# Onju-Home.net
KiCad netlist of a schematic drawn in Altium Designer
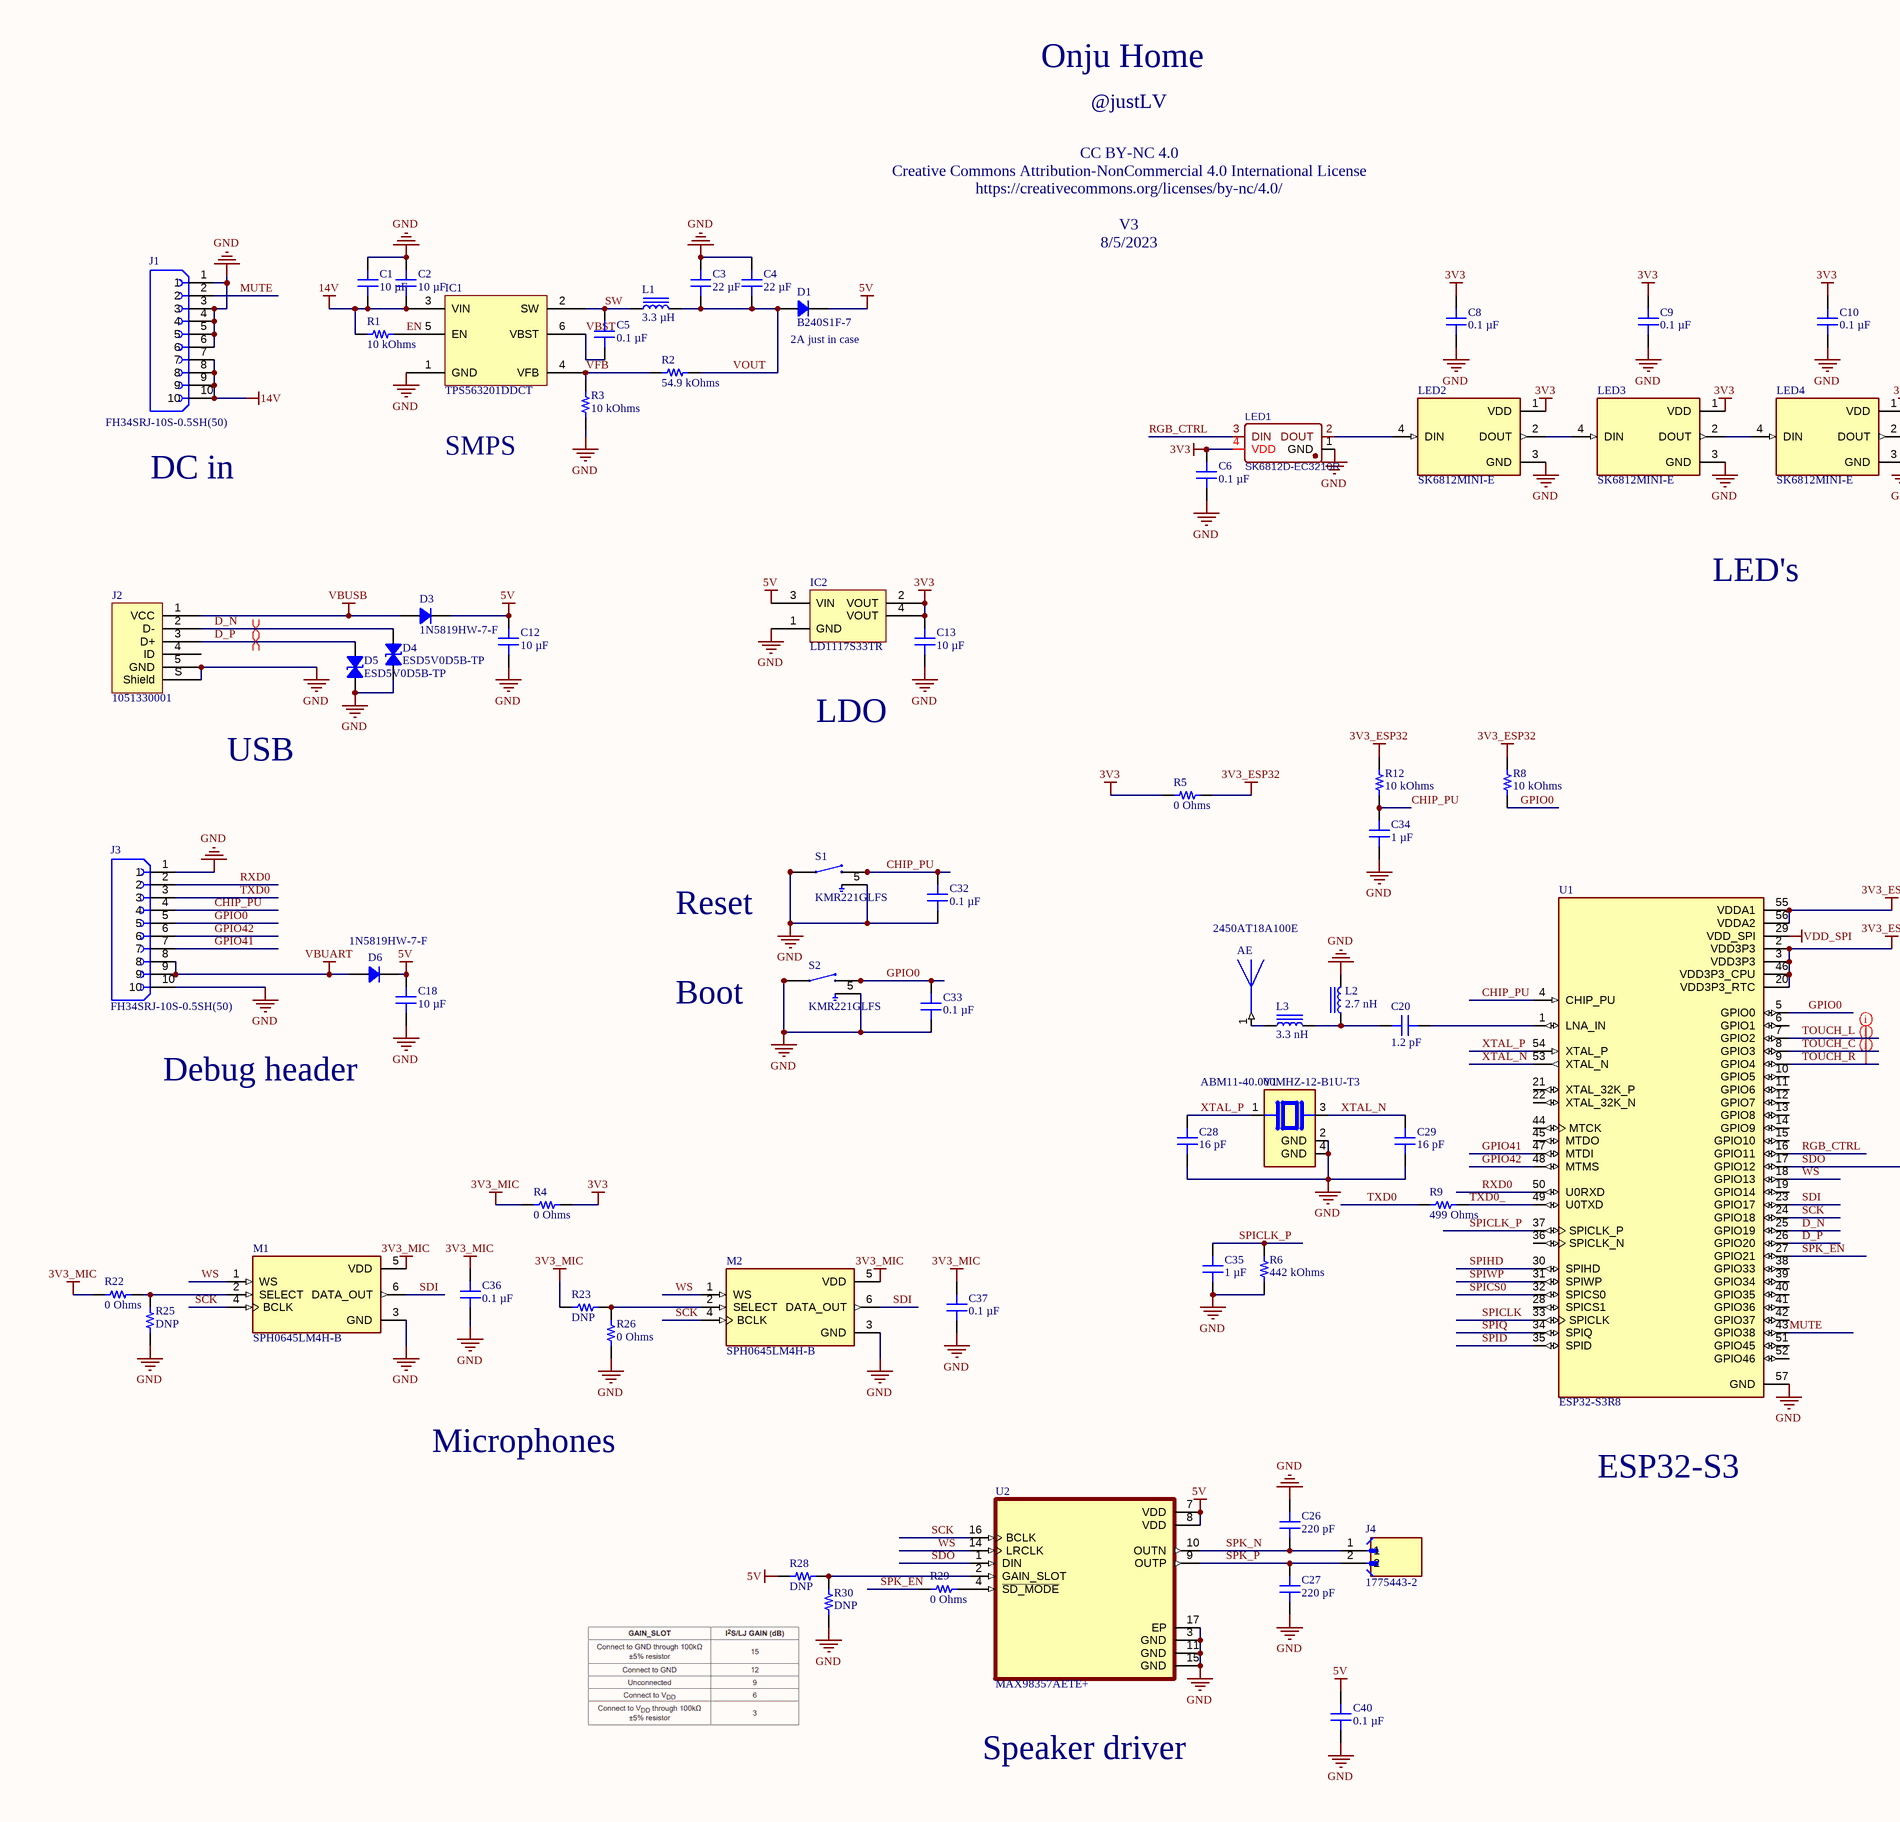
[diagram p0: Onju-Home.SchDoc, left]
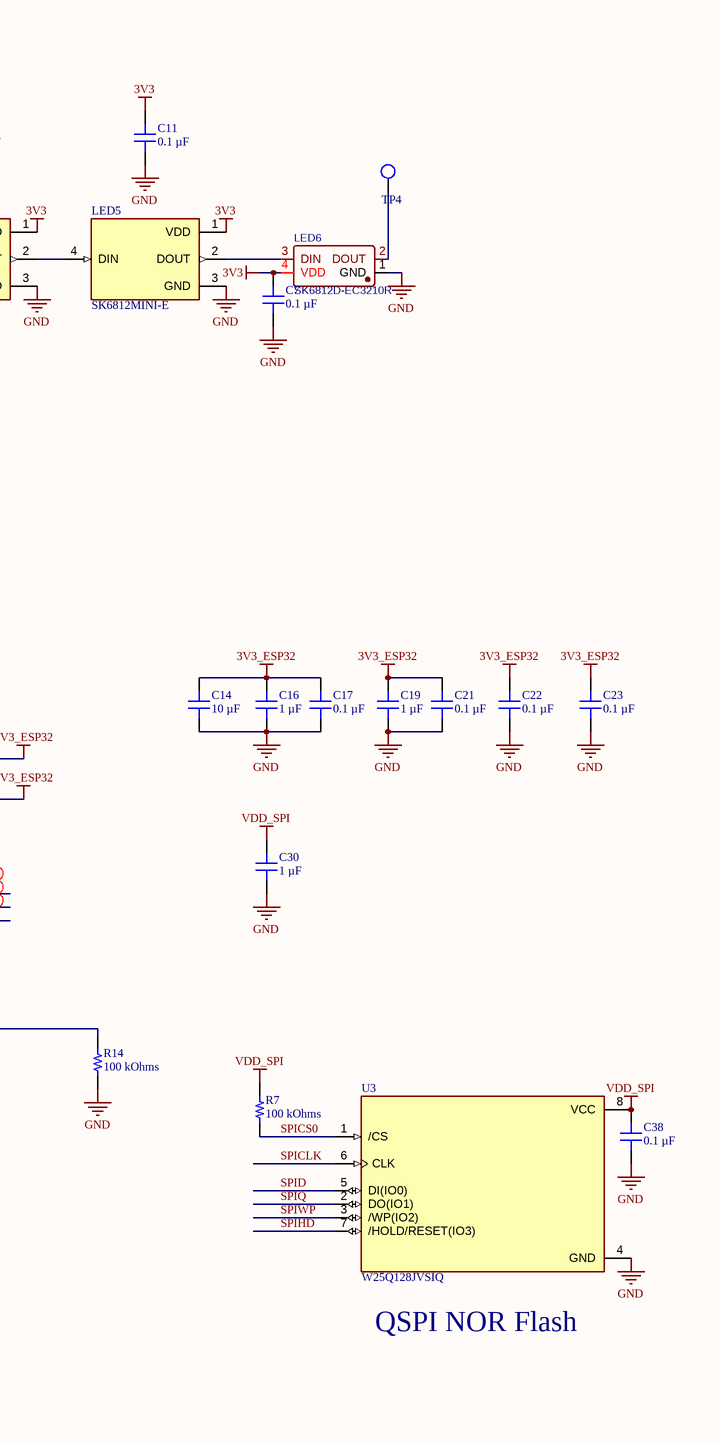
[diagram p1: Onju-Home.SchDoc, right]

(export (version "E")
  (design (tool "Eeschema 10.0.6"))
  (components
    (comp (ref "AE")
      (value "2450AT18A100E")
      (footprint "ANTC3216X140N")
      (description "2.4GHz Chip RF Antenna 2.4GHz ~ 2.5GHz 0.5dBi Solder Surface Mount")
      (fields (field (name "MF") "Johanson Technology") (field (name "JLC PART NUMBER") "C89334"))
      (libsource (lib "Schlib1") (part "2450AT18A100E"))
    )
    (comp (ref "C1")
      (value "10 µF")
      (footprint "CAP 0805_2012")
      (description "CAP CER 10UF 16V X5R 0805")
      (fields
        (field (name "PART NUMBER") "CL21A106KOQNNNE")
        (field (name "MANUFACTURER") "Samsung Electro-Mechanics")
      )
      (libsource (lib "Celestial Altium Library - altium_library") (part "Capacitor"))
    )
    (comp (ref "C2")
      (value "10 µF")
      (footprint "CAP 0805_2012")
      (description "CAP CER 10UF 16V X5R 0805")
      (fields
        (field (name "PART NUMBER") "CL21A106KOQNNNE")
        (field (name "MANUFACTURER") "Samsung Electro-Mechanics")
      )
      (libsource (lib "Celestial Altium Library - altium_library") (part "Capacitor"))
    )
    (comp (ref "C3")
      (value "22 µF")
      (footprint "CAP 0805_2012")
      (description "CAP CER 22UF 25V X5R 0805")
      (fields
        (field (name "PART NUMBER") "CL21A226MAYNNNE")
        (field (name "MANUFACTURER") "Samsung Electro-Mechanics")
      )
      (libsource (lib "Celestial Altium Library - altium_library") (part "Capacitor"))
    )
    (comp (ref "C4")
      (value "22 µF")
      (footprint "CAP 0805_2012")
      (description "CAP CER 22UF 25V X5R 0805")
      (fields
        (field (name "PART NUMBER") "CL21A226MAYNNNE")
        (field (name "MANUFACTURER") "Samsung Electro-Mechanics")
      )
      (libsource (lib "Celestial Altium Library - altium_library") (part "Capacitor"))
    )
    (comp (ref "C5")
      (value "0.1 µF")
      (footprint "CAP 0402_1005")
      (description "CAP CER 0.1UF 25V X5R 0402")
      (fields
        (field (name "PART NUMBER") "CL05A104KA5NNNC")
        (field (name "MANUFACTURER") "Samsung Electro-Mechanics")
      )
      (libsource (lib "Celestial Altium Library - altium_library") (part "Capacitor"))
    )
    (comp (ref "C6")
      (value "0.1 µF")
      (footprint "CAP 0402_1005")
      (description "CAP CER 0.1UF 25V X5R 0402")
      (fields
        (field (name "PART NUMBER") "CL05A104KA5NNNC")
        (field (name "MANUFACTURER") "Samsung Electro-Mechanics")
      )
      (libsource (lib "Celestial Altium Library - altium_library") (part "Capacitor"))
    )
    (comp (ref "C7")
      (value "0.1 µF")
      (footprint "CAP 0402_1005")
      (description "CAP CER 0.1UF 25V X5R 0402")
      (fields
        (field (name "PART NUMBER") "CL05A104KA5NNNC")
        (field (name "MANUFACTURER") "Samsung Electro-Mechanics")
      )
      (libsource (lib "Celestial Altium Library - altium_library") (part "Capacitor"))
    )
    (comp (ref "C8")
      (value "0.1 µF")
      (footprint "CAP 0402_1005")
      (description "CAP CER 0.1UF 25V X5R 0402")
      (fields
        (field (name "PART NUMBER") "CL05A104KA5NNNC")
        (field (name "MANUFACTURER") "Samsung Electro-Mechanics")
      )
      (libsource (lib "Celestial Altium Library - altium_library") (part "Capacitor"))
    )
    (comp (ref "C9")
      (value "0.1 µF")
      (footprint "CAP 0402_1005")
      (description "CAP CER 0.1UF 25V X5R 0402")
      (fields
        (field (name "PART NUMBER") "CL05A104KA5NNNC")
        (field (name "MANUFACTURER") "Samsung Electro-Mechanics")
      )
      (libsource (lib "Celestial Altium Library - altium_library") (part "Capacitor"))
    )
    (comp (ref "C10")
      (value "0.1 µF")
      (footprint "CAP 0402_1005")
      (description "CAP CER 0.1UF 25V X5R 0402")
      (fields
        (field (name "PART NUMBER") "CL05A104KA5NNNC")
        (field (name "MANUFACTURER") "Samsung Electro-Mechanics")
      )
      (libsource (lib "Celestial Altium Library - altium_library") (part "Capacitor"))
    )
    (comp (ref "C11")
      (value "0.1 µF")
      (footprint "CAP 0402_1005")
      (description "CAP CER 0.1UF 25V X5R 0402")
      (fields
        (field (name "PART NUMBER") "CL05A104KA5NNNC")
        (field (name "MANUFACTURER") "Samsung Electro-Mechanics")
      )
      (libsource (lib "Celestial Altium Library - altium_library") (part "Capacitor"))
    )
    (comp (ref "C12")
      (value "10 µF")
      (footprint "CAP 0805_2012")
      (description "CAP CER 10UF 16V X5R 0805")
      (fields
        (field (name "PART NUMBER") "CL21A106KOQNNNE")
        (field (name "MANUFACTURER") "Samsung Electro-Mechanics")
      )
      (libsource (lib "Celestial Altium Library - altium_library") (part "Capacitor"))
    )
    (comp (ref "C13")
      (value "10 µF")
      (footprint "CAP 0805_2012")
      (description "CAP CER 10UF 16V X5R 0805")
      (fields
        (field (name "PART NUMBER") "CL21A106KOQNNNE")
        (field (name "MANUFACTURER") "Samsung Electro-Mechanics")
      )
      (libsource (lib "Celestial Altium Library - altium_library") (part "Capacitor"))
    )
    (comp (ref "C14")
      (value "10 µF")
      (footprint "CAP 0805_2012")
      (description "CAP CER 10UF 16V X5R 0805")
      (fields
        (field (name "PART NUMBER") "CL21A106KOQNNNE")
        (field (name "MANUFACTURER") "Samsung Electro-Mechanics")
      )
      (libsource (lib "Celestial Altium Library - altium_library") (part "Capacitor"))
    )
    (comp (ref "C16")
      (value "1 µF")
      (footprint "CAP 0402_1005")
      (description "CAP CER 1UF 25V X5R 0402")
      (fields
        (field (name "PART NUMBER") "GRM155R61E105MA12J")
        (field (name "MANUFACTURER") "Murata Electronics")
      )
      (libsource (lib "Celestial Altium Library - altium_library") (part "Capacitor"))
    )
    (comp (ref "C17")
      (value "0.1 µF")
      (footprint "CAP 0402_1005")
      (description "CAP CER 0.1UF 25V X5R 0402")
      (fields
        (field (name "PART NUMBER") "CL05A104KA5NNNC")
        (field (name "MANUFACTURER") "Samsung Electro-Mechanics")
      )
      (libsource (lib "Celestial Altium Library - altium_library") (part "Capacitor"))
    )
    (comp (ref "C18")
      (value "10 µF")
      (footprint "CAP 0805_2012")
      (description "CAP CER 10UF 16V X5R 0805")
      (fields
        (field (name "PART NUMBER") "CL21A106KOQNNNE")
        (field (name "MANUFACTURER") "Samsung Electro-Mechanics")
      )
      (libsource (lib "Celestial Altium Library - altium_library") (part "Capacitor"))
    )
    (comp (ref "C19")
      (value "1 µF")
      (footprint "CAP 0402_1005")
      (description "CAP CER 1UF 25V X5R 0402")
      (fields
        (field (name "PART NUMBER") "GRM155R61E105MA12J")
        (field (name "MANUFACTURER") "Murata Electronics")
      )
      (libsource (lib "Celestial Altium Library - altium_library") (part "Capacitor"))
    )
    (comp (ref "C20")
      (value "1.2 pF")
      (footprint "CAP 0402_1005")
      (description "CAP CER 1.2PF 50V C0G/NP0 0402")
      (fields
        (field (name "PART NUMBER") "500R07S1R2BV4T")
        (field (name "MANUFACTURER") "Johanson Technology Inc.")
      )
      (libsource (lib "Celestial Altium Library - altium_library") (part "Capacitor"))
    )
    (comp (ref "C21")
      (value "0.1 µF")
      (footprint "CAP 0402_1005")
      (description "CAP CER 0.1UF 25V X5R 0402")
      (fields
        (field (name "PART NUMBER") "CL05A104KA5NNNC")
        (field (name "MANUFACTURER") "Samsung Electro-Mechanics")
      )
      (libsource (lib "Celestial Altium Library - altium_library") (part "Capacitor"))
    )
    (comp (ref "C22")
      (value "0.1 µF")
      (footprint "CAP 0402_1005")
      (description "CAP CER 0.1UF 25V X5R 0402")
      (fields
        (field (name "PART NUMBER") "CL05A104KA5NNNC")
        (field (name "MANUFACTURER") "Samsung Electro-Mechanics")
      )
      (libsource (lib "Celestial Altium Library - altium_library") (part "Capacitor"))
    )
    (comp (ref "C23")
      (value "0.1 µF")
      (footprint "CAP 0402_1005")
      (description "CAP CER 0.1UF 25V X5R 0402")
      (fields
        (field (name "PART NUMBER") "CL05A104KA5NNNC")
        (field (name "MANUFACTURER") "Samsung Electro-Mechanics")
      )
      (libsource (lib "Celestial Altium Library - altium_library") (part "Capacitor"))
    )
    (comp (ref "C26")
      (value "220 pF")
      (footprint "CAP 0603_1608")
      (description "CAP CER 220PF 50V X7R 0603")
      (fields
        (field (name "PART NUMBER") "CL10B221KB8NFNC")
        (field (name "MANUFACTURER") "Samsung Electro-Mechanics")
      )
      (libsource (lib "Celestial Altium Library - altium_library") (part "Capacitor"))
    )
    (comp (ref "C27")
      (value "220 pF")
      (footprint "CAP 0603_1608")
      (description "CAP CER 220PF 50V X7R 0603")
      (fields
        (field (name "PART NUMBER") "CL10B221KB8NFNC")
        (field (name "MANUFACTURER") "Samsung Electro-Mechanics")
      )
      (libsource (lib "Celestial Altium Library - altium_library") (part "Capacitor"))
    )
    (comp (ref "C28")
      (value "16 pF")
      (footprint "CAP 0402_1005")
      (description "CAP CER 16PF 50V C0G/NP0 0402")
      (fields
        (field (name "PART NUMBER") "GCM1555C1H160FA16D")
        (field (name "MANUFACTURER") "Murata Electronics")
      )
      (libsource (lib "Celestial Altium Library - altium_library") (part "Capacitor"))
    )
    (comp (ref "C29")
      (value "16 pF")
      (footprint "CAP 0402_1005")
      (description "CAP CER 16PF 50V C0G/NP0 0402")
      (fields
        (field (name "PART NUMBER") "GCM1555C1H160FA16D")
        (field (name "MANUFACTURER") "Murata Electronics")
      )
      (libsource (lib "Celestial Altium Library - altium_library") (part "Capacitor"))
    )
    (comp (ref "C30")
      (value "1 µF")
      (footprint "CAP 0402_1005")
      (description "CAP CER 1UF 25V X5R 0402")
      (fields
        (field (name "PART NUMBER") "GRM155R61E105MA12J")
        (field (name "MANUFACTURER") "Murata Electronics")
      )
      (libsource (lib "Celestial Altium Library - altium_library") (part "Capacitor"))
    )
    (comp (ref "C32")
      (value "0.1 µF")
      (footprint "CAP 0402_1005")
      (description "CAP CER 0.1UF 25V X5R 0402")
      (fields
        (field (name "PART NUMBER") "CL05A104KA5NNNC")
        (field (name "MANUFACTURER") "Samsung Electro-Mechanics")
      )
      (libsource (lib "Celestial Altium Library - altium_library") (part "Capacitor"))
    )
    (comp (ref "C33")
      (value "0.1 µF")
      (footprint "CAP 0402_1005")
      (description "CAP CER 0.1UF 25V X5R 0402")
      (fields
        (field (name "PART NUMBER") "CL05A104KA5NNNC")
        (field (name "MANUFACTURER") "Samsung Electro-Mechanics")
      )
      (libsource (lib "Celestial Altium Library - altium_library") (part "Capacitor"))
    )
    (comp (ref "C34")
      (value "1 µF")
      (footprint "CAP 0402_1005")
      (description "CAP CER 1UF 25V X5R 0402")
      (fields
        (field (name "PART NUMBER") "GRM155R61E105MA12J")
        (field (name "MANUFACTURER") "Murata Electronics")
      )
      (libsource (lib "Celestial Altium Library - altium_library") (part "Capacitor"))
    )
    (comp (ref "C35")
      (value "1 µF")
      (footprint "CAP 0402_1005")
      (description "CAP CER 1UF 25V X5R 0402")
      (fields
        (field (name "PART NUMBER") "GRM155R61E105MA12J")
        (field (name "MANUFACTURER") "Murata Electronics")
      )
      (libsource (lib "Celestial Altium Library - altium_library") (part "Capacitor"))
    )
    (comp (ref "C36")
      (value "0.1 µF")
      (footprint "CAP 0402_1005")
      (description "CAP CER 0.1UF 25V X5R 0402")
      (fields
        (field (name "PART NUMBER") "CL05A104KA5NNNC")
        (field (name "MANUFACTURER") "Samsung Electro-Mechanics")
      )
      (libsource (lib "Celestial Altium Library - altium_library") (part "Capacitor"))
    )
    (comp (ref "C37")
      (value "0.1 µF")
      (footprint "CAP 0402_1005")
      (description "CAP CER 0.1UF 25V X5R 0402")
      (fields
        (field (name "PART NUMBER") "CL05A104KA5NNNC")
        (field (name "MANUFACTURER") "Samsung Electro-Mechanics")
      )
      (libsource (lib "Celestial Altium Library - altium_library") (part "Capacitor"))
    )
    (comp (ref "C38")
      (value "0.1 µF")
      (footprint "CAP 0402_1005")
      (description "CAP CER 0.1UF 25V X5R 0402")
      (fields
        (field (name "PART NUMBER") "CL05A104KA5NNNC")
        (field (name "MANUFACTURER") "Samsung Electro-Mechanics")
      )
      (libsource (lib "Celestial Altium Library - altium_library") (part "Capacitor"))
    )
    (comp (ref "C40")
      (value "0.1 µF")
      (footprint "CAP 0402_1005")
      (description "CAP CER 0.1UF 25V X5R 0402")
      (fields
        (field (name "PART NUMBER") "CL05A104KA5NNNC")
        (field (name "MANUFACTURER") "Samsung Electro-Mechanics")
      )
      (libsource (lib "Celestial Altium Library - altium_library") (part "Capacitor"))
    )
    (comp (ref "D1")
      (value "B240S1F-7")
      (footprint "SOD123F")
      (description "DIODE SCHOTTKY 40V 2A SOD123F")
      (fields (field (name "MANUFACTURER") "Diodes Incorporated") (field (name "JLC PART NUMBER") "C3001607"))
      (libsource (lib "Celestial Altium Library - altium_library") (part "Diode"))
    )
    (comp (ref "D3")
      (value "1N5819HW-7-F")
      (footprint "SOD-123")
      (description "DIODE SCHOTTKY 40V 1A SOD123")
      (fields (field (name "MANUFACTURER") "Diodes Incorporated") (field (name "JLC PART NUMBER") "C82544"))
      (libsource (lib "Celestial Altium Library - altium_library") (part "Diode"))
    )
    (comp (ref "D4")
      (value "ESD5V0D5B-TP")
      (footprint "SOD523F")
      (description "TVS DIODE 5VWM 13VC SOD523")
      (libsource (lib "Celestial Altium Library - altium_library") (part "Diode TVS"))
    )
    (comp (ref "D5")
      (value "ESD5V0D5B-TP")
      (footprint "SOD523F")
      (description "TVS DIODE 5VWM 13VC SOD523")
      (libsource (lib "Celestial Altium Library - altium_library") (part "Diode TVS"))
    )
    (comp (ref "D6")
      (value "1N5819HW-7-F")
      (footprint "SOD-123")
      (description "DIODE SCHOTTKY 40V 1A SOD123")
      (fields (field (name "MANUFACTURER") "Diodes Incorporated") (field (name "JLC PART NUMBER") "C82544"))
      (libsource (lib "Celestial Altium Library - altium_library") (part "Diode"))
    )
    (comp (ref "IC1")
      (value "TPS563201DDCT")
      (footprint "TI SOT-23-6 DDC")
      (description "IC REG BUCK ADJ 3A TSOT23-6")
      (fields (field (name "MANUFACTURER") "Texas Instruments"))
      (libsource (lib "Celestial Altium Library - altium_library") (part "TI TPS563201"))
    )
    (comp (ref "IC2")
      (value "LD1117S33TR")
      (footprint "ST SOT-223")
      (description "IC REG LINEAR 3.3V 800MA SOT223")
      (fields (field (name "MANUFACTURER") "STMicroelectronics"))
      (libsource (lib "Celestial Altium Library - altium_library") (part "ST LD1117"))
    )
    (comp (ref "J1")
      (value "FH34SRJ-10S-0.5SH(50)")
      (footprint "HRS_FH34SRJ-10S-0.5SH(50)")
      (fields (field (name "MANUFACTURER") "Hirose"))
      (libsource (lib "Schlib1") (part "FH34SRJ-10S-0.5SH(50)"))
    )
    (comp (ref "J2")
      (value "1051330001")
      (footprint "MOLEX 1051330001")
      (description "CONN RCPT USB2.0 MICRO B SMD")
      (fields (field (name "MANUFACTURER") "Molex"))
      (libsource (lib "Celestial Altium Library - altium_library") (part "USB 2.0 Type B Micro"))
    )
    (comp (ref "J3")
      (value "FH34SRJ-10S-0.5SH(50)")
      (footprint "HRS_FH34SRJ-10S-0.5SH(50)")
      (fields (field (name "MANUFACTURER") "Hirose"))
      (libsource (lib "Schlib1") (part "FH34SRJ-10S-0.5SH(50)"))
    )
    (comp (ref "J4")
      (value "1775443-2")
      (footprint "TE_1775443-2")
      (description "EMIX CONN., 1.5MM PITCH, HDR, V/T, 2P")
      (fields (field (name "MF") "TE Connectivity"))
      (libsource (lib "Schlib1") (part "1775443-2"))
    )
    (comp (ref "L1")
      (value "3.3 µH")
      (footprint "BOURNS SRN4018")
      (description "FIXED IND 3.3UH 2.2A 66 MOHM SMD")
      (fields (field (name "PART NUMBER") "SRN4018-3R3M") (field (name "MANUFACTURER") "Bourns Inc."))
      (libsource (lib "Celestial Altium Library - altium_library") (part "Inductor"))
    )
    (comp (ref "L2")
      (value "2.7 nH")
      (footprint "IND 0402_1005 RF WW")
      (description "FIXED IND 2.7NH 1.5A 47MOHM SMD")
      (fields
        (field (name "PART NUMBER") "LQW15AN2N7C8ZD")
        (field (name "MANUFACTURER") "Murata Electronics")
      )
      (libsource (lib "Celestial Altium Library - altium_library") (part "Inductor"))
    )
    (comp (ref "L3")
      (value "3.3 nH")
      (footprint "IND 0402_1005 RF WW")
      (description "FIXED IND 3.3NH 2A 30 MOHM SMD")
      (fields
        (field (name "PART NUMBER") "LQW15AN3N3C80D")
        (field (name "MANUFACTURER") "Murata Electronics")
      )
      (libsource (lib "Celestial Altium Library - altium_library") (part "Inductor"))
    )
    (comp (ref "LED1")
      (value "SK6812D-EC3210R")
      (footprint "LED-SMD_4P_SK6812D-EC3210R")
      (fields
        (field (name "BOM_SUPPLIER PART") "C2890041")
        (field (name "MANUFACTURER") "OPSCO Optoelectronics")
        (field (name "CONTRIBUTOR") "LCSC")
      )
      (libsource (lib "Schlib1") (part "SK6812D-EC3210R"))
    )
    (comp (ref "LED2")
      (value "SK6812MINI-E")
      (footprint "LED_SK6812-E")
      (description "SK6812MINI-E SMD RGB LED")
      (fields (field (name "MF") "DONGGUANG OPSCO OPTOELECTRONICS CO., LTD") (field (name "MP") "Sk6812-E"))
      (libsource (lib "Schlib1") (part "SK6812MINI-E"))
    )
    (comp (ref "LED3")
      (value "SK6812MINI-E")
      (footprint "LED_SK6812-E")
      (description "SK6812MINI-E SMD RGB LED")
      (fields (field (name "MF") "DONGGUANG OPSCO OPTOELECTRONICS CO., LTD") (field (name "MP") "Sk6812-E"))
      (libsource (lib "Schlib1") (part "SK6812MINI-E"))
    )
    (comp (ref "LED4")
      (value "SK6812MINI-E")
      (footprint "LED_SK6812-E")
      (description "SK6812MINI-E SMD RGB LED")
      (fields (field (name "MF") "DONGGUANG OPSCO OPTOELECTRONICS CO., LTD") (field (name "MP") "Sk6812-E"))
      (libsource (lib "Schlib1") (part "SK6812MINI-E"))
    )
    (comp (ref "LED5")
      (value "SK6812MINI-E")
      (footprint "LED_SK6812-E")
      (description "SK6812MINI-E SMD RGB LED")
      (fields (field (name "MF") "DONGGUANG OPSCO OPTOELECTRONICS CO., LTD") (field (name "MP") "Sk6812-E"))
      (libsource (lib "Schlib1") (part "SK6812MINI-E"))
    )
    (comp (ref "LED6")
      (value "SK6812D-EC3210R")
      (footprint "LED-SMD_4P_SK6812D-EC3210R")
      (fields
        (field (name "BOM_SUPPLIER PART") "C2890041")
        (field (name "MANUFACTURER") "OPSCO Optoelectronics")
        (field (name "CONTRIBUTOR") "LCSC")
      )
      (libsource (lib "Schlib1") (part "SK6812D-EC3210R"))
    )
    (comp (ref "M1")
      (value "SPH0645LM4H-B")
      (footprint "MIC_SPH0645LM4H-B")
      (fields (field (name "DIGI-KEY_PART_NUMBER") "423-1405-1-ND") (field (name "MF") "Knowles"))
      (libsource (lib "Schlib1") (part "SPH0645LM4H-B"))
    )
    (comp (ref "M2")
      (value "SPH0645LM4H-B")
      (footprint "MIC_SPH0645LM4H-B")
      (fields (field (name "DIGI-KEY_PART_NUMBER") "423-1405-1-ND") (field (name "MF") "Knowles"))
      (libsource (lib "Schlib1") (part "SPH0645LM4H-B"))
    )
    (comp (ref "R1")
      (value "10 kOhms")
      (footprint "RES 0603_1608")
      (description "RES 10K OHM 1% 1/10W 0603")
      (fields (field (name "PART NUMBER") "RC0603FR-1010KL") (field (name "MANUFACTURER") "Yageo"))
      (libsource (lib "Celestial Altium Library - altium_library") (part "Resistor"))
    )
    (comp (ref "R2")
      (value "54.9 kOhms")
      (footprint "RES 0603_1608")
      (description "RES 54.9K OHM 1% 1/10W 0603")
      (fields (field (name "PART NUMBER") "RC0603FR-0754K9L") (field (name "MANUFACTURER") "Yageo"))
      (libsource (lib "Celestial Altium Library - altium_library") (part "Resistor"))
    )
    (comp (ref "R3")
      (value "10 kOhms")
      (footprint "RES 0603_1608")
      (description "RES 10K OHM 1% 1/10W 0603")
      (fields (field (name "PART NUMBER") "RC0603FR-1010KL") (field (name "MANUFACTURER") "Yageo"))
      (libsource (lib "Celestial Altium Library - altium_library") (part "Resistor"))
    )
    (comp (ref "R4")
      (value "0 Ohms")
      (footprint "RES 0603_1608")
      (description "RES 0 OHM JUMPER 1/10W 0603")
      (fields (field (name "PART NUMBER") "RC0603JR-130RL") (field (name "MANUFACTURER") "Yageo"))
      (libsource (lib "Celestial Altium Library - altium_library") (part "Resistor"))
    )
    (comp (ref "R5")
      (value "0 Ohms")
      (footprint "RES 0603_1608")
      (description "RES 0 OHM JUMPER 1/10W 0603")
      (fields (field (name "PART NUMBER") "RC0603JR-130RL") (field (name "MANUFACTURER") "Yageo"))
      (libsource (lib "Celestial Altium Library - altium_library") (part "Resistor"))
    )
    (comp (ref "R6")
      (value "442 kOhms")
      (footprint "RES 0603_1608")
      (description "RES 442K OHM 1% 1/10W 0603")
      (fields (field (name "PART NUMBER") "RC0603FR-07442KL") (field (name "MANUFACTURER") "Yageo"))
      (libsource (lib "Celestial Altium Library - altium_library") (part "Resistor"))
    )
    (comp (ref "R7")
      (value "100 kOhms")
      (footprint "RES 0603_1608")
      (description "RES 100K OHM 1% 1/10W 0603")
      (fields (field (name "PART NUMBER") "RC0603FR-07100KL") (field (name "MANUFACTURER") "Yageo"))
      (libsource (lib "Celestial Altium Library - altium_library") (part "Resistor"))
    )
    (comp (ref "R8")
      (value "10 kOhms")
      (footprint "RES 0603_1608")
      (description "RES 10K OHM 1% 1/10W 0603")
      (fields (field (name "PART NUMBER") "RC0603FR-1010KL") (field (name "MANUFACTURER") "Yageo"))
      (libsource (lib "Celestial Altium Library - altium_library") (part "Resistor"))
    )
    (comp (ref "R9")
      (value "499 Ohms")
      (footprint "RES 0402_1005")
      (description "RES 499 OHM 1% 1/16W 0402")
      (fields (field (name "PART NUMBER") "RC0402FR-07499RL") (field (name "MANUFACTURER") "Yageo"))
      (libsource (lib "Celestial Altium Library - altium_library") (part "Resistor"))
    )
    (comp (ref "R12")
      (value "10 kOhms")
      (footprint "RES 0603_1608")
      (description "RES 10K OHM 1% 1/10W 0603")
      (fields (field (name "PART NUMBER") "RC0603FR-1010KL") (field (name "MANUFACTURER") "Yageo"))
      (libsource (lib "Celestial Altium Library - altium_library") (part "Resistor"))
    )
    (comp (ref "R14")
      (value "100 kOhms")
      (footprint "RES 0603_1608")
      (description "RES 100K OHM 1% 1/10W 0603")
      (fields (field (name "PART NUMBER") "RC0603FR-07100KL") (field (name "MANUFACTURER") "Yageo"))
      (libsource (lib "Celestial Altium Library - altium_library") (part "Resistor"))
    )
    (comp (ref "R22")
      (value "0 Ohms")
      (footprint "RES 0603_1608")
      (description "RES 0 OHM JUMPER 1/10W 0603")
      (fields (field (name "PART NUMBER") "RC0603JR-130RL") (field (name "MANUFACTURER") "Yageo"))
      (libsource (lib "Celestial Altium Library - altium_library") (part "Resistor"))
    )
    (comp (ref "R23")
      (value "DNP")
      (footprint "RES 0603_1608")
      (description "RES 0 OHM JUMPER 1/10W 0603")
      (fields (field (name "PART NUMBER") "RC0603JR-130RL") (field (name "MANUFACTURER") "Yageo"))
      (libsource (lib "Celestial Altium Library - altium_library") (part "Resistor"))
    )
    (comp (ref "R25")
      (value "DNP")
      (footprint "RES 0603_1608")
      (description "RES 0 OHM JUMPER 1/10W 0603")
      (fields (field (name "PART NUMBER") "RC0603JR-130RL") (field (name "MANUFACTURER") "Yageo"))
      (libsource (lib "Celestial Altium Library - altium_library") (part "Resistor"))
    )
    (comp (ref "R26")
      (value "0 Ohms")
      (footprint "RES 0603_1608")
      (description "RES 0 OHM JUMPER 1/10W 0603")
      (fields (field (name "PART NUMBER") "RC0603JR-130RL") (field (name "MANUFACTURER") "Yageo"))
      (libsource (lib "Celestial Altium Library - altium_library") (part "Resistor"))
    )
    (comp (ref "R28")
      (value "DNP")
      (footprint "RES 0603_1608")
      (description "RES 0 OHM JUMPER 1/10W 0603")
      (fields (field (name "PART NUMBER") "RC0603JR-130RL") (field (name "MANUFACTURER") "Yageo"))
      (libsource (lib "Celestial Altium Library - altium_library") (part "Resistor"))
    )
    (comp (ref "R29")
      (value "0 Ohms")
      (footprint "RES 0603_1608")
      (description "RES 0 OHM JUMPER 1/10W 0603")
      (fields (field (name "PART NUMBER") "RC0603JR-130RL") (field (name "MANUFACTURER") "Yageo"))
      (libsource (lib "Celestial Altium Library - altium_library") (part "Resistor"))
    )
    (comp (ref "R30")
      (value "DNP")
      (footprint "RES 0603_1608")
      (description "RES 0 OHM JUMPER 1/10W 0603")
      (fields (field (name "PART NUMBER") "RC0603JR-130RL") (field (name "MANUFACTURER") "Yageo"))
      (libsource (lib "Celestial Altium Library - altium_library") (part "Resistor"))
    )
    (comp (ref "S1")
      (value "KMR221GLFS")
      (footprint "SW_KMR221GLFS")
      (description "Switch Tactile N.O. SPST Button Gull Wing 0.05A 32VDC 1VA 200000Cycles 2N SMD Automotive T/R")
      (fields (field (name "MANUFACTURER") "C&K") (field (name "JLC PART NUMBER") "C72443"))
      (libsource (lib "Schlib1") (part "KMR221GLFS"))
    )
    (comp (ref "S2")
      (value "KMR221GLFS")
      (footprint "SW_KMR221GLFS")
      (description "Switch Tactile N.O. SPST Button Gull Wing 0.05A 32VDC 1VA 200000Cycles 2N SMD Automotive T/R")
      (fields (field (name "MANUFACTURER") "C&K") (field (name "JLC PART NUMBER") "C72443"))
      (libsource (lib "Schlib1") (part "KMR221GLFS"))
    )
    (comp (ref "TP4") (value "TP") (footprint "TP_1MM") (libsource (lib "Schlib1") (part "TP")))
    (comp (ref "U1")
      (value "ESP32-S3R8")
      (footprint "QFN40P700X700X90-57N")
      (fields
        (field (name "DIGI-KEY_PART_NUMBER") "1904-ESP32-S3R8-ND")
        (field (name "MF") "Espressif Systems")
      )
      (libsource (lib "Schlib1") (part "ESP32-S3R8"))
    )
    (comp (ref "U2")
      (value "MAX98357AETE+")
      (footprint "QFN50P300X300X80-17N")
      (description "Amplifier IC 1-Channel _Mono_ Class D 16-TQFN _3x3_")
      (fields (field (name "MF") "Maxim Integrated") (field (name "MANUFACTURER") "Analog Devices"))
      (libsource (lib "Schlib1") (part "MAX98357AETE+"))
    )
    (comp (ref "U3")
      (value "W25Q128JVSIQ")
      (footprint "SOIC127P790X216-8N")
      (description "FLASH - NOR Memory IC 128Mb (16M x 8) SPI - Quad I/O, QPI, DTR 133 MHz 8-SOIC")
      (fields (field (name "MF") "Winbond Electronics"))
      (libsource (lib "Schlib1") (part "W25Q128JVSIQ"))
    )
    (comp (ref "Y1")
      (value "ABM11-40.000MHZ-12-B1U-T3")
      (footprint "XTAL_ABM11-40.000MHZ-12-B1U-T3")
      (description "Crystal 40MHz Â±10ppm (Tol) Â±10ppm (Stability) 12pF FUND 60Ohm 4-Pin Ultra Mini-CSMD T/R")
      (fields (field (name "MF") "Abracon Corporation") (field (name "JLC PART NUMBER") "C255899"))
      (libsource (lib "Schlib1") (part "ABM11-40.000MHZ-12-B1U-T3"))
    )
  )
  (nets
    (net (code "1") (name "/CHIP_PU") (class "Default")
      (node (ref "C32") (pin "2") (pinfunction "2_2") (pintype "passive"))
      (node (ref "C34") (pin "2") (pinfunction "2_2") (pintype "passive"))
      (node (ref "J3") (pin "4") (pinfunction "4_4") (pintype "passive"))
      (node (ref "R12") (pin "2") (pinfunction "2_2") (pintype "passive"))
      (node (ref "S1") (pin "2") (pinfunction "3_2") (pintype "passive"))
      (node (ref "S1") (pin "3") (pinfunction "3_3") (pintype "passive"))
      (node (ref "U1") (pin "4") (pinfunction "CHIP_PU_4") (pintype "input"))
    )
    (net (code "2") (name "/D_N") (class "Default")
      (node (ref "D4") (pin "2") (pinfunction "2_2") (pintype "passive"))
      (node (ref "J2") (pin "2") (pinfunction "D-_2") (pintype "passive"))
      (node (ref "U1") (pin "25") (pinfunction "GPIO19_25") (pintype "bidirectional"))
    )
    (net (code "3") (name "/D_P") (class "Default")
      (node (ref "D5") (pin "2") (pinfunction "2_2") (pintype "passive"))
      (node (ref "J2") (pin "3") (pinfunction "D+_3") (pintype "passive"))
      (node (ref "U1") (pin "26") (pinfunction "GPIO20_26") (pintype "bidirectional"))
    )
    (net (code "4") (name "/EN") (class "Default")
      (node (ref "IC1") (pin "5") (pinfunction "EN_5") (pintype "passive"))
      (node (ref "R1") (pin "1") (pinfunction "1_1") (pintype "passive"))
    )
    (net (code "5") (name "/GPIO0") (class "Default")
      (node (ref "C33") (pin "2") (pinfunction "2_2") (pintype "passive"))
      (node (ref "J3") (pin "5") (pinfunction "5_5") (pintype "passive"))
      (node (ref "R8") (pin "2") (pinfunction "2_2") (pintype "passive"))
      (node (ref "S2") (pin "2") (pinfunction "3_2") (pintype "passive"))
      (node (ref "S2") (pin "3") (pinfunction "3_3") (pintype "passive"))
      (node (ref "U1") (pin "5") (pinfunction "GPIO0_5") (pintype "bidirectional"))
    )
    (net (code "6") (name "/GPIO41") (class "Default")
      (node (ref "J3") (pin "7") (pinfunction "7_7") (pintype "passive"))
      (node (ref "U1") (pin "47") (pinfunction "MTDI_47") (pintype "bidirectional"))
    )
    (net (code "7") (name "/GPIO42") (class "Default")
      (node (ref "J3") (pin "6") (pinfunction "6_6") (pintype "passive"))
      (node (ref "U1") (pin "48") (pinfunction "MTMS_48") (pintype "bidirectional"))
    )
    (net (code "8") (name "/MUTE") (class "Default")
      (node (ref "J1") (pin "2") (pinfunction "2_2") (pintype "passive"))
      (node (ref "U1") (pin "43") (pinfunction "GPIO38_43") (pintype "bidirectional"))
    )
    (net (code "9") (name "/RGB_CTRL") (class "Default")
      (node (ref "LED1") (pin "3") (pinfunction "DIN_3") (pintype "passive"))
      (node (ref "U1") (pin "16") (pinfunction "GPIO11_16") (pintype "bidirectional"))
    )
    (net (code "10") (name "/RXD0") (class "Default")
      (node (ref "J3") (pin "2") (pinfunction "2_2") (pintype "passive"))
      (node (ref "U1") (pin "50") (pinfunction "U0RXD_50") (pintype "bidirectional"))
    )
    (net (code "11") (name "/SCK") (class "Default")
      (node (ref "M1") (pin "4") (pinfunction "BCLK_4") (pintype "input"))
      (node (ref "M2") (pin "4") (pinfunction "BCLK_4") (pintype "input"))
      (node (ref "U1") (pin "24") (pinfunction "GPIO18_24") (pintype "bidirectional"))
      (node (ref "U2") (pin "16") (pinfunction "BCLK_16") (pintype "input"))
    )
    (net (code "12") (name "/SDI") (class "Default")
      (node (ref "M1") (pin "6") (pinfunction "DATA_OUT_6") (pintype "output"))
      (node (ref "M2") (pin "6") (pinfunction "DATA_OUT_6") (pintype "output"))
      (node (ref "U1") (pin "23") (pinfunction "GPIO17_23") (pintype "bidirectional"))
    )
    (net (code "13") (name "/SDO") (class "Default")
      (node (ref "R14") (pin "1") (pinfunction "1_1") (pintype "passive"))
      (node (ref "U1") (pin "17") (pinfunction "GPIO12_17") (pintype "bidirectional"))
      (node (ref "U2") (pin "1") (pinfunction "DIN_1") (pintype "input"))
    )
    (net (code "14") (name "/SPICLK") (class "Default")
      (node (ref "U1") (pin "33") (pinfunction "SPICLK_33") (pintype "bidirectional"))
      (node (ref "U3") (pin "6") (pinfunction "CLK_6") (pintype "input"))
    )
    (net (code "15") (name "/SPICLK_P") (class "Default")
      (node (ref "C35") (pin "2") (pinfunction "2_2") (pintype "passive"))
      (node (ref "R6") (pin "2") (pinfunction "2_2") (pintype "passive"))
      (node (ref "U1") (pin "37") (pinfunction "SPICLK_P_37") (pintype "bidirectional"))
    )
    (net (code "16") (name "/SPICS0") (class "Default")
      (node (ref "R7") (pin "2") (pinfunction "2_2") (pintype "passive"))
      (node (ref "U1") (pin "32") (pinfunction "SPICS0_32") (pintype "bidirectional"))
      (node (ref "U3") (pin "1") (pinfunction "/CS_1") (pintype "input"))
    )
    (net (code "17") (name "/SPID") (class "Default")
      (node (ref "U1") (pin "35") (pinfunction "SPID_35") (pintype "bidirectional"))
      (node (ref "U3") (pin "5") (pinfunction "DI(IO0)_5") (pintype "bidirectional"))
    )
    (net (code "18") (name "/SPIHD") (class "Default")
      (node (ref "U1") (pin "30") (pinfunction "SPIHD_30") (pintype "bidirectional"))
      (node (ref "U3") (pin "7") (pinfunction "/HOLD/RESET(IO3)_7") (pintype "bidirectional"))
    )
    (net (code "19") (name "/SPIQ") (class "Default")
      (node (ref "U1") (pin "34") (pinfunction "SPIQ_34") (pintype "bidirectional"))
      (node (ref "U3") (pin "2") (pinfunction "DO(IO1)_2") (pintype "bidirectional"))
    )
    (net (code "20") (name "/SPIWP") (class "Default")
      (node (ref "U1") (pin "31") (pinfunction "SPIWP_31") (pintype "bidirectional"))
      (node (ref "U3") (pin "3") (pinfunction "/WP(IO2)_3") (pintype "bidirectional"))
    )
    (net (code "21") (name "/SPK_EN") (class "Default")
      (node (ref "R29") (pin "1") (pinfunction "1_1") (pintype "passive"))
      (node (ref "U1") (pin "27") (pinfunction "GPIO21_27") (pintype "bidirectional"))
    )
    (net (code "22") (name "/SPK_N") (class "Default")
      (node (ref "C26") (pin "1") (pinfunction "1_1") (pintype "passive"))
      (node (ref "J4") (pin "1") (pinfunction "1_1") (pintype "passive"))
      (node (ref "U2") (pin "10") (pinfunction "OUTN_10") (pintype "output"))
    )
    (net (code "23") (name "/SPK_P") (class "Default")
      (node (ref "C27") (pin "2") (pinfunction "2_2") (pintype "passive"))
      (node (ref "J4") (pin "2") (pinfunction "2_2") (pintype "passive"))
      (node (ref "U2") (pin "9") (pinfunction "OUTP_9") (pintype "output"))
    )
    (net (code "24") (name "/SW") (class "Default")
      (node (ref "C5") (pin "2") (pinfunction "2_2") (pintype "passive"))
      (node (ref "IC1") (pin "2") (pinfunction "SW_2") (pintype "passive"))
      (node (ref "L1") (pin "1") (pinfunction "1_1") (pintype "passive"))
    )
    (net (code "25") (name "/TOUCH_C") (class "Default")
      (node (ref "U1") (pin "8") (pinfunction "GPIO3_8") (pintype "bidirectional"))
    )
    (net (code "26") (name "/TOUCH_L") (class "Default")
      (node (ref "U1") (pin "7") (pinfunction "GPIO2_7") (pintype "bidirectional"))
    )
    (net (code "27") (name "/TOUCH_R") (class "Default")
      (node (ref "U1") (pin "9") (pinfunction "GPIO4_9") (pintype "bidirectional"))
    )
    (net (code "28") (name "/TXD0") (class "Default")
      (node (ref "J3") (pin "3") (pinfunction "3_3") (pintype "passive"))
      (node (ref "R9") (pin "1") (pinfunction "1_1") (pintype "passive"))
    )
    (net (code "29") (name "/TXD0_") (class "Default")
      (node (ref "R9") (pin "2") (pinfunction "2_2") (pintype "passive"))
      (node (ref "U1") (pin "49") (pinfunction "U0TXD_49") (pintype "bidirectional"))
    )
    (net (code "30") (name "/VBST") (class "Default")
      (node (ref "C5") (pin "1") (pinfunction "1_1") (pintype "passive"))
      (node (ref "IC1") (pin "6") (pinfunction "VBST_6") (pintype "passive"))
    )
    (net (code "31") (name "/VFB") (class "Default")
      (node (ref "IC1") (pin "4") (pinfunction "VFB_4") (pintype "passive"))
      (node (ref "R2") (pin "1") (pinfunction "1_1") (pintype "passive"))
      (node (ref "R3") (pin "2") (pinfunction "2_2") (pintype "passive"))
    )
    (net (code "32") (name "/VOUT") (class "Default")
      (node (ref "C3") (pin "1") (pinfunction "1_1") (pintype "passive"))
      (node (ref "C4") (pin "1") (pinfunction "1_1") (pintype "passive"))
      (node (ref "D1") (pin "1") (pinfunction "1_1") (pintype "passive"))
      (node (ref "L1") (pin "2") (pinfunction "2_2") (pintype "passive"))
      (node (ref "R2") (pin "2") (pinfunction "2_2") (pintype "passive"))
    )
    (net (code "33") (name "/WS") (class "Default")
      (node (ref "M1") (pin "1") (pinfunction "WS_1") (pintype "input"))
      (node (ref "M2") (pin "1") (pinfunction "WS_1") (pintype "input"))
      (node (ref "U1") (pin "18") (pinfunction "GPIO13_18") (pintype "bidirectional"))
      (node (ref "U2") (pin "14") (pinfunction "LRCLK_14") (pintype "input"))
    )
    (net (code "34") (name "/XTAL_N") (class "Default")
      (node (ref "C29") (pin "2") (pinfunction "2_2") (pintype "passive"))
      (node (ref "U1") (pin "53") (pinfunction "XTAL_N_53") (pintype "output"))
      (node (ref "Y1") (pin "3") (pinfunction "2_3") (pintype "passive"))
    )
    (net (code "35") (name "/XTAL_P") (class "Default")
      (node (ref "C28") (pin "2") (pinfunction "2_2") (pintype "passive"))
      (node (ref "U1") (pin "54") (pinfunction "XTAL_P_54") (pintype "input"))
      (node (ref "Y1") (pin "1") (pinfunction "1_1") (pintype "passive"))
    )
    (net (code "36") (name "3V3") (class "Default")
      (node (ref "C10") (pin "2") (pinfunction "2_2") (pintype "passive"))
      (node (ref "C11") (pin "2") (pinfunction "2_2") (pintype "passive"))
      (node (ref "C13") (pin "1") (pinfunction "1_1") (pintype "passive"))
      (node (ref "C6") (pin "2") (pinfunction "2_2") (pintype "passive"))
      (node (ref "C7") (pin "2") (pinfunction "2_2") (pintype "passive"))
      (node (ref "C8") (pin "2") (pinfunction "2_2") (pintype "passive"))
      (node (ref "C9") (pin "2") (pinfunction "2_2") (pintype "passive"))
      (node (ref "IC2") (pin "2") (pinfunction "VOUT_2") (pintype "passive"))
      (node (ref "IC2") (pin "4") (pinfunction "VOUT_4") (pintype "passive"))
      (node (ref "LED1") (pin "4") (pinfunction "VDD_4") (pintype "passive"))
      (node (ref "LED2") (pin "1") (pinfunction "VDD_1") (pintype "power_in"))
      (node (ref "LED3") (pin "1") (pinfunction "VDD_1") (pintype "power_in"))
      (node (ref "LED4") (pin "1") (pinfunction "VDD_1") (pintype "power_in"))
      (node (ref "LED5") (pin "1") (pinfunction "VDD_1") (pintype "power_in"))
      (node (ref "LED6") (pin "4") (pinfunction "VDD_4") (pintype "passive"))
      (node (ref "R4") (pin "2") (pinfunction "2_2") (pintype "passive"))
      (node (ref "R5") (pin "1") (pinfunction "1_1") (pintype "passive"))
    )
    (net (code "37") (name "3V3_ESP32") (class "Default")
      (node (ref "C14") (pin "1") (pinfunction "1_1") (pintype "passive"))
      (node (ref "C16") (pin "2") (pinfunction "2_2") (pintype "passive"))
      (node (ref "C17") (pin "2") (pinfunction "2_2") (pintype "passive"))
      (node (ref "C19") (pin "2") (pinfunction "2_2") (pintype "passive"))
      (node (ref "C21") (pin "2") (pinfunction "2_2") (pintype "passive"))
      (node (ref "C22") (pin "2") (pinfunction "2_2") (pintype "passive"))
      (node (ref "C23") (pin "2") (pinfunction "2_2") (pintype "passive"))
      (node (ref "R12") (pin "1") (pinfunction "1_1") (pintype "passive"))
      (node (ref "R5") (pin "2") (pinfunction "2_2") (pintype "passive"))
      (node (ref "R8") (pin "1") (pinfunction "1_1") (pintype "passive"))
      (node (ref "U1") (pin "2") (pinfunction "VDD3P3_2") (pintype "power_in"))
      (node (ref "U1") (pin "20") (pinfunction "VDD3P3_RTC_20") (pintype "power_in"))
      (node (ref "U1") (pin "3") (pinfunction "VDD3P3_3") (pintype "power_in"))
      (node (ref "U1") (pin "46") (pinfunction "VDD3P3_CPU_46") (pintype "power_in"))
      (node (ref "U1") (pin "55") (pinfunction "VDDA1_55") (pintype "power_in"))
      (node (ref "U1") (pin "56") (pinfunction "VDDA2_56") (pintype "power_in"))
    )
    (net (code "38") (name "3V3_MIC") (class "Default")
      (node (ref "C36") (pin "2") (pinfunction "2_2") (pintype "passive"))
      (node (ref "C37") (pin "2") (pinfunction "2_2") (pintype "passive"))
      (node (ref "M1") (pin "5") (pinfunction "VDD_5") (pintype "power_in"))
      (node (ref "M2") (pin "5") (pinfunction "VDD_5") (pintype "power_in"))
      (node (ref "R22") (pin "1") (pinfunction "1_1") (pintype "passive"))
      (node (ref "R23") (pin "2") (pinfunction "2_2") (pintype "passive"))
      (node (ref "R4") (pin "1") (pinfunction "1_1") (pintype "passive"))
    )
    (net (code "39") (name "5V") (class "Default")
      (node (ref "C12") (pin "1") (pinfunction "1_1") (pintype "passive"))
      (node (ref "C18") (pin "1") (pinfunction "1_1") (pintype "passive"))
      (node (ref "C40") (pin "2") (pinfunction "2_2") (pintype "passive"))
      (node (ref "D1") (pin "2") (pinfunction "2_2") (pintype "passive"))
      (node (ref "D3") (pin "2") (pinfunction "2_2") (pintype "passive"))
      (node (ref "D6") (pin "2") (pinfunction "2_2") (pintype "passive"))
      (node (ref "IC2") (pin "3") (pinfunction "VIN_3") (pintype "passive"))
      (node (ref "R28") (pin "2") (pinfunction "2_2") (pintype "passive"))
      (node (ref "U2") (pin "7") (pinfunction "VDD_7") (pintype "power_in"))
      (node (ref "U2") (pin "8") (pinfunction "VDD_8") (pintype "power_in"))
    )
    (net (code "40") (name "14V") (class "Default")
      (node (ref "C1") (pin "1") (pinfunction "1_1") (pintype "passive"))
      (node (ref "C2") (pin "1") (pinfunction "1_1") (pintype "passive"))
      (node (ref "IC1") (pin "3") (pinfunction "VIN_3") (pintype "passive"))
      (node (ref "J1") (pin "10") (pinfunction "10_10") (pintype "passive"))
      (node (ref "J1") (pin "7") (pinfunction "7_7") (pintype "passive"))
      (node (ref "J1") (pin "8") (pinfunction "8_8") (pintype "passive"))
      (node (ref "J1") (pin "9") (pinfunction "9_9") (pintype "passive"))
      (node (ref "R1") (pin "2") (pinfunction "2_2") (pintype "passive"))
    )
    (net (code "41") (name "GND") (class "Default")
      (node (ref "C1") (pin "2") (pinfunction "2_2") (pintype "passive"))
      (node (ref "C10") (pin "1") (pinfunction "1_1") (pintype "passive"))
      (node (ref "C11") (pin "1") (pinfunction "1_1") (pintype "passive"))
      (node (ref "C12") (pin "2") (pinfunction "2_2") (pintype "passive"))
      (node (ref "C13") (pin "2") (pinfunction "2_2") (pintype "passive"))
      (node (ref "C14") (pin "2") (pinfunction "2_2") (pintype "passive"))
      (node (ref "C16") (pin "1") (pinfunction "1_1") (pintype "passive"))
      (node (ref "C17") (pin "1") (pinfunction "1_1") (pintype "passive"))
      (node (ref "C18") (pin "2") (pinfunction "2_2") (pintype "passive"))
      (node (ref "C19") (pin "1") (pinfunction "1_1") (pintype "passive"))
      (node (ref "C2") (pin "2") (pinfunction "2_2") (pintype "passive"))
      (node (ref "C21") (pin "1") (pinfunction "1_1") (pintype "passive"))
      (node (ref "C22") (pin "1") (pinfunction "1_1") (pintype "passive"))
      (node (ref "C23") (pin "1") (pinfunction "1_1") (pintype "passive"))
      (node (ref "C26") (pin "2") (pinfunction "2_2") (pintype "passive"))
      (node (ref "C27") (pin "1") (pinfunction "1_1") (pintype "passive"))
      (node (ref "C28") (pin "1") (pinfunction "1_1") (pintype "passive"))
      (node (ref "C29") (pin "1") (pinfunction "1_1") (pintype "passive"))
      (node (ref "C3") (pin "2") (pinfunction "2_2") (pintype "passive"))
      (node (ref "C30") (pin "1") (pinfunction "1_1") (pintype "passive"))
      (node (ref "C32") (pin "1") (pinfunction "1_1") (pintype "passive"))
      (node (ref "C33") (pin "1") (pinfunction "1_1") (pintype "passive"))
      (node (ref "C34") (pin "1") (pinfunction "1_1") (pintype "passive"))
      (node (ref "C35") (pin "1") (pinfunction "1_1") (pintype "passive"))
      (node (ref "C36") (pin "1") (pinfunction "1_1") (pintype "passive"))
      (node (ref "C37") (pin "1") (pinfunction "1_1") (pintype "passive"))
      (node (ref "C38") (pin "1") (pinfunction "1_1") (pintype "passive"))
      (node (ref "C4") (pin "2") (pinfunction "2_2") (pintype "passive"))
      (node (ref "C40") (pin "1") (pinfunction "1_1") (pintype "passive"))
      (node (ref "C6") (pin "1") (pinfunction "1_1") (pintype "passive"))
      (node (ref "C7") (pin "1") (pinfunction "1_1") (pintype "passive"))
      (node (ref "C8") (pin "1") (pinfunction "1_1") (pintype "passive"))
      (node (ref "C9") (pin "1") (pinfunction "1_1") (pintype "passive"))
      (node (ref "D4") (pin "1") (pinfunction "1_1") (pintype "passive"))
      (node (ref "D5") (pin "1") (pinfunction "1_1") (pintype "passive"))
      (node (ref "IC1") (pin "1") (pinfunction "GND_1") (pintype "passive"))
      (node (ref "IC2") (pin "1") (pinfunction "GND_1") (pintype "passive"))
      (node (ref "J1") (pin "1") (pinfunction "1_1") (pintype "passive"))
      (node (ref "J1") (pin "3") (pinfunction "3_3") (pintype "passive"))
      (node (ref "J1") (pin "4") (pinfunction "4_4") (pintype "passive"))
      (node (ref "J1") (pin "5") (pinfunction "5_5") (pintype "passive"))
      (node (ref "J1") (pin "6") (pinfunction "6_6") (pintype "passive"))
      (node (ref "J2") (pin "5") (pinfunction "GND_5") (pintype "passive"))
      (node (ref "J2") (pin "S") (pinfunction "Shield_S") (pintype "passive"))
      (node (ref "J3") (pin "1") (pinfunction "1_1") (pintype "passive"))
      (node (ref "J3") (pin "10") (pinfunction "10_10") (pintype "passive"))
      (node (ref "L2") (pin "2") (pinfunction "2_2") (pintype "passive"))
      (node (ref "LED1") (pin "1") (pinfunction "GND_1") (pintype "passive"))
      (node (ref "LED2") (pin "3") (pinfunction "GND_3") (pintype "power_in"))
      (node (ref "LED3") (pin "3") (pinfunction "GND_3") (pintype "power_in"))
      (node (ref "LED4") (pin "3") (pinfunction "GND_3") (pintype "power_in"))
      (node (ref "LED5") (pin "3") (pinfunction "GND_3") (pintype "power_in"))
      (node (ref "LED6") (pin "1") (pinfunction "GND_1") (pintype "passive"))
      (node (ref "M1") (pin "3") (pinfunction "GND_3") (pintype "power_in"))
      (node (ref "M2") (pin "3") (pinfunction "GND_3") (pintype "power_in"))
      (node (ref "R14") (pin "2") (pinfunction "2_2") (pintype "passive"))
      (node (ref "R25") (pin "1") (pinfunction "1_1") (pintype "passive"))
      (node (ref "R26") (pin "1") (pinfunction "1_1") (pintype "passive"))
      (node (ref "R3") (pin "1") (pinfunction "1_1") (pintype "passive"))
      (node (ref "R30") (pin "1") (pinfunction "1_1") (pintype "passive"))
      (node (ref "R6") (pin "1") (pinfunction "1_1") (pintype "passive"))
      (node (ref "S1") (pin "1") (pinfunction "1_1") (pintype "passive"))
      (node (ref "S1") (pin "4") (pinfunction "1_4") (pintype "passive"))
      (node (ref "S1") (pin "5") (pinfunction "5_5") (pintype "passive"))
      (node (ref "S2") (pin "1") (pinfunction "1_1") (pintype "passive"))
      (node (ref "S2") (pin "4") (pinfunction "1_4") (pintype "passive"))
      (node (ref "S2") (pin "5") (pinfunction "5_5") (pintype "passive"))
      (node (ref "U1") (pin "57") (pinfunction "GND_57") (pintype "power_in"))
      (node (ref "U2") (pin "11") (pinfunction "GND_11") (pintype "power_in"))
      (node (ref "U2") (pin "15") (pinfunction "GND_15") (pintype "power_in"))
      (node (ref "U2") (pin "17") (pinfunction "EP_17") (pintype "power_in"))
      (node (ref "U2") (pin "3") (pinfunction "GND_3") (pintype "power_in"))
      (node (ref "U3") (pin "4") (pinfunction "GND_4") (pintype "power_in"))
      (node (ref "Y1") (pin "2") (pinfunction "GND_2") (pintype "power_in"))
      (node (ref "Y1") (pin "4") (pinfunction "GND_4") (pintype "power_in"))
    )
    (net (code "42") (name "Net-(AE-Pad1)") (class "Default")
      (node (ref "AE") (pin "1") (pinfunction "1_1") (pintype "input"))
      (node (ref "L3") (pin "1") (pinfunction "1_1") (pintype "passive"))
    )
    (net (code "43") (name "Net-(C20-Pad1)") (class "Default")
      (node (ref "C20") (pin "1") (pinfunction "1_1") (pintype "passive"))
      (node (ref "L2") (pin "1") (pinfunction "1_1") (pintype "passive"))
      (node (ref "L3") (pin "2") (pinfunction "2_2") (pintype "passive"))
    )
    (net (code "44") (name "Net-(LED1-DOUT)") (class "Default")
      (node (ref "LED1") (pin "2") (pinfunction "DOUT_2") (pintype "passive"))
      (node (ref "LED2") (pin "4") (pinfunction "DIN_4") (pintype "input"))
    )
    (net (code "45") (name "Net-(LED2-DOUT)") (class "Default")
      (node (ref "LED2") (pin "2") (pinfunction "DOUT_2") (pintype "output"))
      (node (ref "LED3") (pin "4") (pinfunction "DIN_4") (pintype "input"))
    )
    (net (code "46") (name "Net-(LED3-DOUT)") (class "Default")
      (node (ref "LED3") (pin "2") (pinfunction "DOUT_2") (pintype "output"))
      (node (ref "LED4") (pin "4") (pinfunction "DIN_4") (pintype "input"))
    )
    (net (code "47") (name "Net-(LED4-DOUT)") (class "Default")
      (node (ref "LED4") (pin "2") (pinfunction "DOUT_2") (pintype "output"))
      (node (ref "LED5") (pin "4") (pinfunction "DIN_4") (pintype "input"))
    )
    (net (code "48") (name "Net-(LED5-DOUT)") (class "Default")
      (node (ref "LED5") (pin "2") (pinfunction "DOUT_2") (pintype "output"))
      (node (ref "LED6") (pin "3") (pinfunction "DIN_3") (pintype "passive"))
    )
    (net (code "49") (name "Net-(LED6-DOUT)") (class "Default")
      (node (ref "LED6") (pin "2") (pinfunction "DOUT_2") (pintype "passive"))
      (node (ref "TP4") (pin "1") (pinfunction "1_1") (pintype "passive"))
    )
    (net (code "50") (name "Net-(M1-SELECT)") (class "Default")
      (node (ref "M1") (pin "2") (pinfunction "SELECT_2") (pintype "input"))
      (node (ref "R22") (pin "2") (pinfunction "2_2") (pintype "passive"))
      (node (ref "R25") (pin "2") (pinfunction "2_2") (pintype "passive"))
    )
    (net (code "51") (name "Net-(M2-SELECT)") (class "Default")
      (node (ref "M2") (pin "2") (pinfunction "SELECT_2") (pintype "input"))
      (node (ref "R23") (pin "1") (pinfunction "1_1") (pintype "passive"))
      (node (ref "R26") (pin "2") (pinfunction "2_2") (pintype "passive"))
    )
    (net (code "52") (name "Net-(U1-LNA_IN)") (class "Default")
      (node (ref "C20") (pin "2") (pinfunction "2_2") (pintype "passive"))
      (node (ref "U1") (pin "1") (pinfunction "LNA_IN_1") (pintype "bidirectional"))
    )
    (net (code "53") (name "Net-(U2-GAIN_SLOT)") (class "Default")
      (node (ref "R28") (pin "1") (pinfunction "1_1") (pintype "passive"))
      (node (ref "R30") (pin "2") (pinfunction "2_2") (pintype "passive"))
      (node (ref "U2") (pin "2") (pinfunction "GAIN_SLOT_2") (pintype "input"))
    )
    (net (code "54") (name "Net-(U2-~{SD_MODE})") (class "Default")
      (node (ref "R29") (pin "2") (pinfunction "2_2") (pintype "passive"))
      (node (ref "U2") (pin "4") (pinfunction "~{SD_MODE}_4") (pintype "input"))
    )
    (net (code "55") (name "VBUART") (class "Default")
      (node (ref "D6") (pin "1") (pinfunction "1_1") (pintype "passive"))
      (node (ref "J3") (pin "8") (pinfunction "8_8") (pintype "passive"))
      (node (ref "J3") (pin "9") (pinfunction "9_9") (pintype "passive"))
    )
    (net (code "56") (name "VBUSB") (class "Default")
      (node (ref "D3") (pin "1") (pinfunction "1_1") (pintype "passive"))
      (node (ref "J2") (pin "1") (pinfunction "VCC_1") (pintype "passive"))
    )
    (net (code "57") (name "VDD_SPI") (class "Default")
      (node (ref "C30") (pin "2") (pinfunction "2_2") (pintype "passive"))
      (node (ref "C38") (pin "2") (pinfunction "2_2") (pintype "passive"))
      (node (ref "R7") (pin "1") (pinfunction "1_1") (pintype "passive"))
      (node (ref "U1") (pin "29") (pinfunction "VDD_SPI_29") (pintype "power_in"))
      (node (ref "U3") (pin "8") (pinfunction "VCC_8") (pintype "power_in"))
    )
    (net (code "58") (name "unconnected-(J2-ID-Pad4)") (class "Default")
      (node (ref "J2") (pin "4") (pinfunction "ID_4") (pintype "passive"))
    )
    (net (code "59") (name "unconnected-(U1-GPIO1-Pad6)") (class "Default")
      (node (ref "U1") (pin "6") (pinfunction "GPIO1_6") (pintype "bidirectional"))
    )
    (net (code "60") (name "unconnected-(U1-GPIO5-Pad10)") (class "Default")
      (node (ref "U1") (pin "10") (pinfunction "GPIO5_10") (pintype "bidirectional"))
    )
    (net (code "61") (name "unconnected-(U1-GPIO6-Pad11)") (class "Default")
      (node (ref "U1") (pin "11") (pinfunction "GPIO6_11") (pintype "bidirectional"))
    )
    (net (code "62") (name "unconnected-(U1-GPIO7-Pad12)") (class "Default")
      (node (ref "U1") (pin "12") (pinfunction "GPIO7_12") (pintype "bidirectional"))
    )
    (net (code "63") (name "unconnected-(U1-GPIO8-Pad13)") (class "Default")
      (node (ref "U1") (pin "13") (pinfunction "GPIO8_13") (pintype "bidirectional"))
    )
    (net (code "64") (name "unconnected-(U1-GPIO9-Pad14)") (class "Default")
      (node (ref "U1") (pin "14") (pinfunction "GPIO9_14") (pintype "bidirectional"))
    )
    (net (code "65") (name "unconnected-(U1-GPIO10-Pad15)") (class "Default")
      (node (ref "U1") (pin "15") (pinfunction "GPIO10_15") (pintype "bidirectional"))
    )
    (net (code "66") (name "unconnected-(U1-GPIO14-Pad19)") (class "Default")
      (node (ref "U1") (pin "19") (pinfunction "GPIO14_19") (pintype "bidirectional"))
    )
    (net (code "67") (name "unconnected-(U1-GPIO33-Pad38)") (class "Default")
      (node (ref "U1") (pin "38") (pinfunction "GPIO33_38") (pintype "bidirectional"))
    )
    (net (code "68") (name "unconnected-(U1-GPIO34-Pad39)") (class "Default")
      (node (ref "U1") (pin "39") (pinfunction "GPIO34_39") (pintype "bidirectional"))
    )
    (net (code "69") (name "unconnected-(U1-GPIO35-Pad40)") (class "Default")
      (node (ref "U1") (pin "40") (pinfunction "GPIO35_40") (pintype "bidirectional"))
    )
    (net (code "70") (name "unconnected-(U1-GPIO36-Pad41)") (class "Default")
      (node (ref "U1") (pin "41") (pinfunction "GPIO36_41") (pintype "bidirectional"))
    )
    (net (code "71") (name "unconnected-(U1-GPIO37-Pad42)") (class "Default")
      (node (ref "U1") (pin "42") (pinfunction "GPIO37_42") (pintype "bidirectional"))
    )
    (net (code "72") (name "unconnected-(U1-GPIO45-Pad51)") (class "Default")
      (node (ref "U1") (pin "51") (pinfunction "GPIO45_51") (pintype "bidirectional"))
    )
    (net (code "73") (name "unconnected-(U1-GPIO46-Pad52)") (class "Default")
      (node (ref "U1") (pin "52") (pinfunction "GPIO46_52") (pintype "bidirectional"))
    )
    (net (code "74") (name "unconnected-(U1-MTCK-Pad44)") (class "Default")
      (node (ref "U1") (pin "44") (pinfunction "MTCK_44") (pintype "bidirectional"))
    )
    (net (code "75") (name "unconnected-(U1-MTDO-Pad45)") (class "Default")
      (node (ref "U1") (pin "45") (pinfunction "MTDO_45") (pintype "bidirectional"))
    )
    (net (code "76") (name "unconnected-(U1-SPICLK_N-Pad36)") (class "Default")
      (node (ref "U1") (pin "36") (pinfunction "SPICLK_N_36") (pintype "bidirectional"))
    )
    (net (code "77") (name "unconnected-(U1-SPICS1-Pad28)") (class "Default")
      (node (ref "U1") (pin "28") (pinfunction "SPICS1_28") (pintype "bidirectional"))
    )
    (net (code "78") (name "unconnected-(U1-XTAL_32K_N-Pad22)") (class "Default")
      (node (ref "U1") (pin "22") (pinfunction "XTAL_32K_N_22") (pintype "bidirectional"))
    )
    (net (code "79") (name "unconnected-(U1-XTAL_32K_P-Pad21)") (class "Default")
      (node (ref "U1") (pin "21") (pinfunction "XTAL_32K_P_21") (pintype "bidirectional"))
    )
  )
)
